# icewerx_Carrier.net
KiCad netlist of a schematic drawn in EAGLE
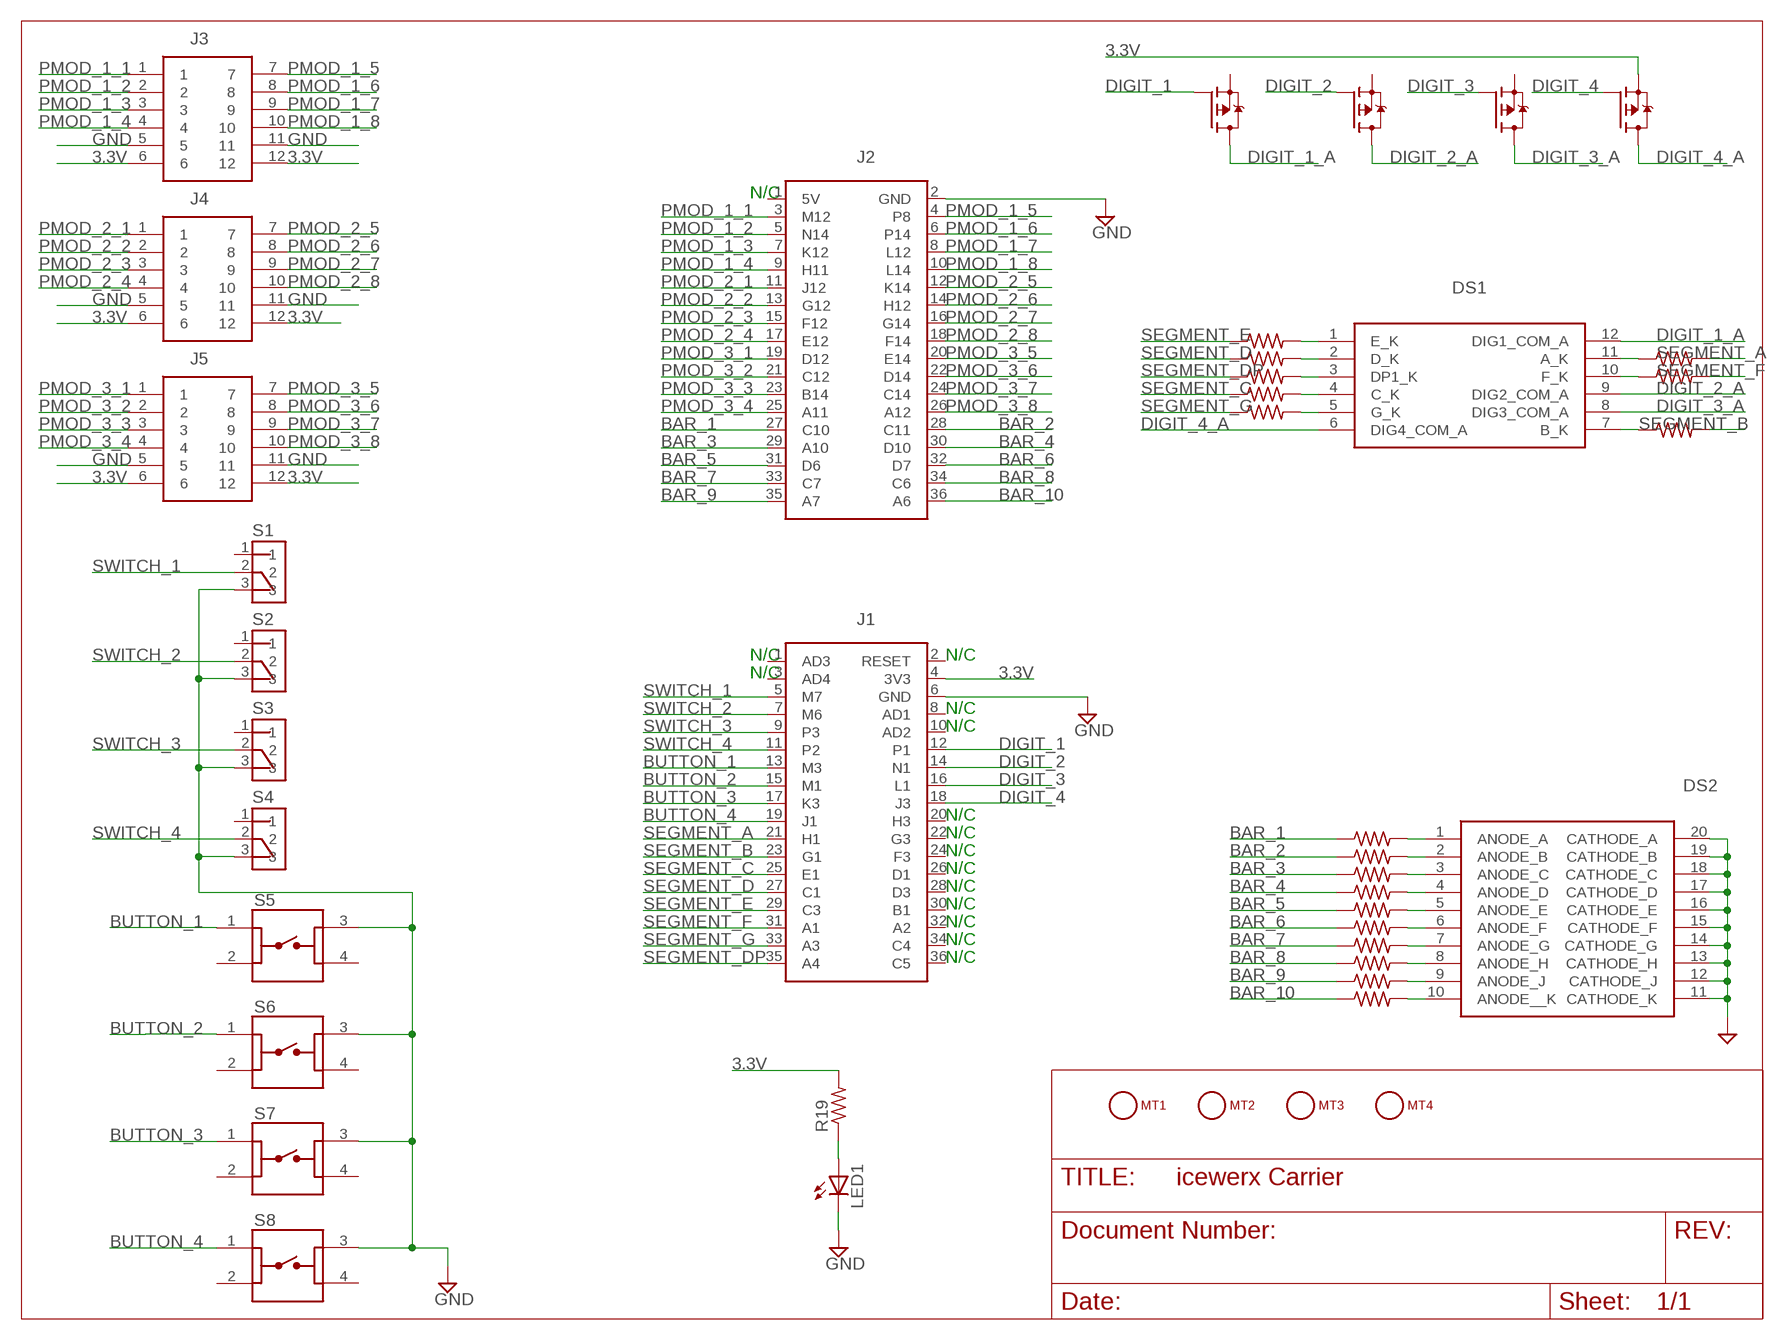
[diagram p0: schematic, sheet 1]

(export (version "E")
  (design (tool "Eeschema 10.0.6"))
  (components
    (comp (ref "DS1")
      (value "LDQ-M282RI")
      (footprint "eagle-import:LDQM282RI")
      (fields (field (name "MOUSER_PART_NUMBER") "696-LDQ-M282RI"))
      (libsource (lib "eagle-import") (part "LDQ-M282RI"))
    )
    (comp (ref "DS2")
      (value "LTA-1000G")
      (footprint "eagle-import:DIPS762W50P254L2527H825Q20N")
      (fields (field (name "MOUSER_PART_NUMBER") "859-LTA-1000G"))
      (libsource (lib "eagle-import") (part "LTA-1000G"))
    )
    (comp (ref "J1")
      (value "ICEWERX-PL2")
      (footprint "eagle-import:TE_4-1734506-1")
      (libsource (lib "eagle-import") (part "ICEWERX-PL2"))
    )
    (comp (ref "J2")
      (value "ICEWERX-PL3")
      (footprint "eagle-import:TE_4-1734506-1")
      (libsource (lib "eagle-import") (part "ICEWERX-PL3"))
    )
    (comp (ref "J3")
      (value "PMOD-SOCKET-FOR-HOST-BOARD")
      (footprint "eagle-import:PMOD-SOCKET-FOR-HOST-BOARD")
      (libsource (lib "eagle-import") (part "PMOD-SOCKET-FOR-HOST-BOARD"))
    )
    (comp (ref "J4")
      (value "PMOD-SOCKET-FOR-HOST-BOARD")
      (footprint "eagle-import:PMOD-SOCKET-FOR-HOST-BOARD")
      (libsource (lib "eagle-import") (part "PMOD-SOCKET-FOR-HOST-BOARD"))
    )
    (comp (ref "J5")
      (value "PMOD-SOCKET-FOR-HOST-BOARD")
      (footprint "eagle-import:PMOD-SOCKET-FOR-HOST-BOARD")
      (libsource (lib "eagle-import") (part "PMOD-SOCKET-FOR-HOST-BOARD"))
    )
    (comp (ref "LED1")
      (value "LED5MM")
      (footprint "eagle-import:LED5MM")
      (libsource (lib "eagle-import") (part "LED5MM"))
    )
    (comp (ref "MT1")
      (value "MOUNTING_HOLE-125_250_ROUND")
      (footprint "eagle-import:MT_125_250")
      (libsource (lib "eagle-import") (part "MOUNTING_HOLE-125_250_ROUND"))
    )
    (comp (ref "MT2")
      (value "MOUNTING_HOLE-125_250_ROUND")
      (footprint "eagle-import:MT_125_250")
      (libsource (lib "eagle-import") (part "MOUNTING_HOLE-125_250_ROUND"))
    )
    (comp (ref "MT3")
      (value "MOUNTING_HOLE-125_250_ROUND")
      (footprint "eagle-import:MT_125_250")
      (libsource (lib "eagle-import") (part "MOUNTING_HOLE-125_250_ROUND"))
    )
    (comp (ref "MT4")
      (value "MOUNTING_HOLE-125_250_ROUND")
      (footprint "eagle-import:MT_125_250")
      (libsource (lib "eagle-import") (part "MOUNTING_HOLE-125_250_ROUND"))
    )
    (comp (ref "Q1")
      (value "NX2301P")
      (footprint "eagle-import:SOT95P230X110-3N")
      (fields (field (name "MANUFACTURER") "Nexperia"))
      (libsource (lib "eagle-import") (part "NX2301P"))
    )
    (comp (ref "Q2")
      (value "NX2301P")
      (footprint "eagle-import:SOT95P230X110-3N")
      (fields (field (name "MANUFACTURER") "Nexperia"))
      (libsource (lib "eagle-import") (part "NX2301P"))
    )
    (comp (ref "Q3")
      (value "NX2301P")
      (footprint "eagle-import:SOT95P230X110-3N")
      (fields (field (name "MANUFACTURER") "Nexperia"))
      (libsource (lib "eagle-import") (part "NX2301P"))
    )
    (comp (ref "Q4")
      (value "NX2301P")
      (footprint "eagle-import:SOT95P230X110-3N")
      (fields (field (name "MANUFACTURER") "Nexperia"))
      (libsource (lib "eagle-import") (part "NX2301P"))
    )
    (comp (ref "R1")
      (value "R-US_0204/5")
      (footprint "eagle-import:0204_5")
      (libsource (lib "eagle-import") (part "R-US_0204/5"))
    )
    (comp (ref "R2")
      (value "R-US_0204/5")
      (footprint "eagle-import:0204_5")
      (libsource (lib "eagle-import") (part "R-US_0204/5"))
    )
    (comp (ref "R3")
      (value "R-US_0204/5")
      (footprint "eagle-import:0204_5")
      (libsource (lib "eagle-import") (part "R-US_0204/5"))
    )
    (comp (ref "R4")
      (value "R-US_0204/5")
      (footprint "eagle-import:0204_5")
      (libsource (lib "eagle-import") (part "R-US_0204/5"))
    )
    (comp (ref "R5")
      (value "R-US_0204/5")
      (footprint "eagle-import:0204_5")
      (libsource (lib "eagle-import") (part "R-US_0204/5"))
    )
    (comp (ref "R6")
      (value "R-US_0204/5")
      (footprint "eagle-import:0204_5")
      (libsource (lib "eagle-import") (part "R-US_0204/5"))
    )
    (comp (ref "R7")
      (value "R-US_0204/5")
      (footprint "eagle-import:0204_5")
      (libsource (lib "eagle-import") (part "R-US_0204/5"))
    )
    (comp (ref "R8")
      (value "R-US_0204/5")
      (footprint "eagle-import:0204_5")
      (libsource (lib "eagle-import") (part "R-US_0204/5"))
    )
    (comp (ref "R9")
      (value "R-US_0204/5")
      (footprint "eagle-import:0204_5")
      (libsource (lib "eagle-import") (part "R-US_0204/5"))
    )
    (comp (ref "R10")
      (value "R-US_0204/5")
      (footprint "eagle-import:0204_5")
      (libsource (lib "eagle-import") (part "R-US_0204/5"))
    )
    (comp (ref "R11")
      (value "R-US_0204/5")
      (footprint "eagle-import:0204_5")
      (libsource (lib "eagle-import") (part "R-US_0204/5"))
    )
    (comp (ref "R12")
      (value "R-US_0204/5")
      (footprint "eagle-import:0204_5")
      (libsource (lib "eagle-import") (part "R-US_0204/5"))
    )
    (comp (ref "R13")
      (value "R-US_0204/5")
      (footprint "eagle-import:0204_5")
      (libsource (lib "eagle-import") (part "R-US_0204/5"))
    )
    (comp (ref "R14")
      (value "R-US_0204/5")
      (footprint "eagle-import:0204_5")
      (libsource (lib "eagle-import") (part "R-US_0204/5"))
    )
    (comp (ref "R15")
      (value "R-US_0204/5")
      (footprint "eagle-import:0204_5")
      (libsource (lib "eagle-import") (part "R-US_0204/5"))
    )
    (comp (ref "R16")
      (value "R-US_0204/5")
      (footprint "eagle-import:0204_5")
      (libsource (lib "eagle-import") (part "R-US_0204/5"))
    )
    (comp (ref "R17")
      (value "R-US_0204/5")
      (footprint "eagle-import:0204_5")
      (libsource (lib "eagle-import") (part "R-US_0204/5"))
    )
    (comp (ref "R18")
      (value "R-US_0204/5")
      (footprint "eagle-import:0204_5")
      (libsource (lib "eagle-import") (part "R-US_0204/5"))
    )
    (comp (ref "R19")
      (value "R-US_0204/5")
      (footprint "eagle-import:0204_5")
      (libsource (lib "eagle-import") (part "R-US_0204/5"))
    )
    (comp (ref "S1")
      (value "OS102011MS2QN1")
      (footprint "eagle-import:SW_OS102011MS2QN1")
      (fields (field (name "MANUFACTURER") "C&K"))
      (libsource (lib "eagle-import") (part "OS102011MS2QN1"))
    )
    (comp (ref "S2")
      (value "OS102011MS2QN1")
      (footprint "eagle-import:SW_OS102011MS2QN1")
      (fields (field (name "MANUFACTURER") "C&K"))
      (libsource (lib "eagle-import") (part "OS102011MS2QN1"))
    )
    (comp (ref "S3")
      (value "OS102011MS2QN1")
      (footprint "eagle-import:SW_OS102011MS2QN1")
      (fields (field (name "MANUFACTURER") "C&K"))
      (libsource (lib "eagle-import") (part "OS102011MS2QN1"))
    )
    (comp (ref "S4")
      (value "OS102011MS2QN1")
      (footprint "eagle-import:SW_OS102011MS2QN1")
      (fields (field (name "MANUFACTURER") "C&K"))
      (libsource (lib "eagle-import") (part "OS102011MS2QN1"))
    )
    (comp (ref "S5")
      (value "1825910-7")
      (footprint "eagle-import:SW_1825910-7")
      (fields (field (name "MANUFACTURER") "TE Connectivity"))
      (libsource (lib "eagle-import") (part "1825910-7"))
    )
    (comp (ref "S6")
      (value "1825910-7")
      (footprint "eagle-import:SW_1825910-7")
      (fields (field (name "MANUFACTURER") "TE Connectivity"))
      (libsource (lib "eagle-import") (part "1825910-7"))
    )
    (comp (ref "S7")
      (value "1825910-7")
      (footprint "eagle-import:SW_1825910-7")
      (fields (field (name "MANUFACTURER") "TE Connectivity"))
      (libsource (lib "eagle-import") (part "1825910-7"))
    )
    (comp (ref "S8")
      (value "1825910-7")
      (footprint "eagle-import:SW_1825910-7")
      (fields (field (name "MANUFACTURER") "TE Connectivity"))
      (libsource (lib "eagle-import") (part "1825910-7"))
    )
  )
  (nets
    (net (code "1") (name "/3.3V") (class "Default")
      (node (ref "J1") (pin "4") (pinfunction "3V3_4") (pintype "bidirectional"))
      (node (ref "J3") (pin "12") (pinfunction "12_12") (pintype "bidirectional"))
      (node (ref "J3") (pin "6") (pinfunction "6_6") (pintype "bidirectional"))
      (node (ref "J4") (pin "12") (pinfunction "12_12") (pintype "bidirectional"))
      (node (ref "J4") (pin "6") (pinfunction "6_6") (pintype "bidirectional"))
      (node (ref "J5") (pin "12") (pinfunction "12_12") (pintype "bidirectional"))
      (node (ref "J5") (pin "6") (pinfunction "6_6") (pintype "bidirectional"))
      (node (ref "Q4") (pin "2") (pinfunction "S_2") (pintype "passive"))
      (node (ref "R19") (pin "2") (pinfunction "2_2") (pintype "passive"))
    )
    (net (code "2") (name "/BAR_1") (class "Default")
      (node (ref "J2") (pin "27") (pinfunction "C10_27") (pintype "bidirectional"))
      (node (ref "R1") (pin "1") (pinfunction "1_1") (pintype "passive"))
    )
    (net (code "3") (name "/BAR_2") (class "Default")
      (node (ref "J2") (pin "28") (pinfunction "C11_28") (pintype "bidirectional"))
      (node (ref "R2") (pin "1") (pinfunction "1_1") (pintype "passive"))
    )
    (net (code "4") (name "/BAR_3") (class "Default")
      (node (ref "J2") (pin "29") (pinfunction "A10_29") (pintype "bidirectional"))
      (node (ref "R3") (pin "1") (pinfunction "1_1") (pintype "passive"))
    )
    (net (code "5") (name "/BAR_4") (class "Default")
      (node (ref "J2") (pin "30") (pinfunction "D10_30") (pintype "bidirectional"))
      (node (ref "R5") (pin "1") (pinfunction "1_1") (pintype "passive"))
    )
    (net (code "6") (name "/BAR_5") (class "Default")
      (node (ref "J2") (pin "31") (pinfunction "D6_31") (pintype "bidirectional"))
      (node (ref "R4") (pin "1") (pinfunction "1_1") (pintype "passive"))
    )
    (net (code "7") (name "/BAR_6") (class "Default")
      (node (ref "J2") (pin "32") (pinfunction "D7_32") (pintype "bidirectional"))
      (node (ref "R6") (pin "1") (pinfunction "1_1") (pintype "passive"))
    )
    (net (code "8") (name "/BAR_7") (class "Default")
      (node (ref "J2") (pin "33") (pinfunction "C7_33") (pintype "bidirectional"))
      (node (ref "R7") (pin "1") (pinfunction "1_1") (pintype "passive"))
    )
    (net (code "9") (name "/BAR_8") (class "Default")
      (node (ref "J2") (pin "34") (pinfunction "C6_34") (pintype "bidirectional"))
      (node (ref "R8") (pin "1") (pinfunction "1_1") (pintype "passive"))
    )
    (net (code "10") (name "/BAR_9") (class "Default")
      (node (ref "J2") (pin "35") (pinfunction "A7_35") (pintype "bidirectional"))
      (node (ref "R10") (pin "1") (pinfunction "1_1") (pintype "passive"))
    )
    (net (code "11") (name "/BAR_10") (class "Default")
      (node (ref "J2") (pin "36") (pinfunction "A6_36") (pintype "bidirectional"))
      (node (ref "R9") (pin "1") (pinfunction "1_1") (pintype "passive"))
    )
    (net (code "12") (name "/BUTTON_1") (class "Default")
      (node (ref "J1") (pin "13") (pinfunction "M3_13") (pintype "bidirectional"))
      (node (ref "S5") (pin "1") (pinfunction "1_1") (pintype "passive"))
    )
    (net (code "13") (name "/BUTTON_2") (class "Default")
      (node (ref "J1") (pin "15") (pinfunction "M1_15") (pintype "bidirectional"))
      (node (ref "S6") (pin "1") (pinfunction "1_1") (pintype "passive"))
    )
    (net (code "14") (name "/BUTTON_3") (class "Default")
      (node (ref "J1") (pin "17") (pinfunction "K3_17") (pintype "bidirectional"))
      (node (ref "S7") (pin "1") (pinfunction "1_1") (pintype "passive"))
    )
    (net (code "15") (name "/BUTTON_4") (class "Default")
      (node (ref "J1") (pin "19") (pinfunction "J1_19") (pintype "bidirectional"))
      (node (ref "S8") (pin "1") (pinfunction "1_1") (pintype "passive"))
    )
    (net (code "16") (name "/DIGIT_1") (class "Default")
      (node (ref "J1") (pin "12") (pinfunction "P1_12") (pintype "bidirectional"))
      (node (ref "Q1") (pin "1") (pinfunction "G_1") (pintype "passive"))
    )
    (net (code "17") (name "/DIGIT_1_A") (class "Default")
      (node (ref "DS1") (pin "12") (pinfunction "DIG1_COM_A_12") (pintype "bidirectional"))
      (node (ref "Q1") (pin "3") (pinfunction "D_3") (pintype "passive"))
    )
    (net (code "18") (name "/DIGIT_2") (class "Default")
      (node (ref "J1") (pin "14") (pinfunction "N1_14") (pintype "bidirectional"))
      (node (ref "Q2") (pin "1") (pinfunction "G_1") (pintype "passive"))
    )
    (net (code "19") (name "/DIGIT_2_A") (class "Default")
      (node (ref "DS1") (pin "9") (pinfunction "DIG2_COM_A_9") (pintype "bidirectional"))
      (node (ref "Q2") (pin "3") (pinfunction "D_3") (pintype "passive"))
    )
    (net (code "20") (name "/DIGIT_3") (class "Default")
      (node (ref "J1") (pin "16") (pinfunction "L1_16") (pintype "bidirectional"))
      (node (ref "Q3") (pin "1") (pinfunction "G_1") (pintype "passive"))
    )
    (net (code "21") (name "/DIGIT_3_A") (class "Default")
      (node (ref "DS1") (pin "8") (pinfunction "DIG3_COM_A_8") (pintype "bidirectional"))
      (node (ref "Q3") (pin "3") (pinfunction "D_3") (pintype "passive"))
    )
    (net (code "22") (name "/DIGIT_4") (class "Default")
      (node (ref "J1") (pin "18") (pinfunction "J3_18") (pintype "bidirectional"))
      (node (ref "Q4") (pin "1") (pinfunction "G_1") (pintype "passive"))
    )
    (net (code "23") (name "/DIGIT_4_A") (class "Default")
      (node (ref "DS1") (pin "6") (pinfunction "DIG4_COM_A_6") (pintype "bidirectional"))
      (node (ref "Q4") (pin "3") (pinfunction "D_3") (pintype "passive"))
    )
    (net (code "24") (name "/PMOD_1_1") (class "Default")
      (node (ref "J2") (pin "3") (pinfunction "M12_3") (pintype "bidirectional"))
      (node (ref "J3") (pin "1") (pinfunction "1_1") (pintype "bidirectional"))
    )
    (net (code "25") (name "/PMOD_1_2") (class "Default")
      (node (ref "J2") (pin "5") (pinfunction "N14_5") (pintype "bidirectional"))
      (node (ref "J3") (pin "2") (pinfunction "2_2") (pintype "bidirectional"))
    )
    (net (code "26") (name "/PMOD_1_3") (class "Default")
      (node (ref "J2") (pin "7") (pinfunction "K12_7") (pintype "bidirectional"))
      (node (ref "J3") (pin "3") (pinfunction "3_3") (pintype "bidirectional"))
    )
    (net (code "27") (name "/PMOD_1_4") (class "Default")
      (node (ref "J2") (pin "9") (pinfunction "H11_9") (pintype "bidirectional"))
      (node (ref "J3") (pin "4") (pinfunction "4_4") (pintype "bidirectional"))
    )
    (net (code "28") (name "/PMOD_1_5") (class "Default")
      (node (ref "J2") (pin "4") (pinfunction "P8_4") (pintype "bidirectional"))
      (node (ref "J3") (pin "7") (pinfunction "7_7") (pintype "bidirectional"))
    )
    (net (code "29") (name "/PMOD_1_6") (class "Default")
      (node (ref "J2") (pin "6") (pinfunction "P14_6") (pintype "bidirectional"))
      (node (ref "J3") (pin "8") (pinfunction "8_8") (pintype "bidirectional"))
    )
    (net (code "30") (name "/PMOD_1_7") (class "Default")
      (node (ref "J2") (pin "8") (pinfunction "L12_8") (pintype "bidirectional"))
      (node (ref "J3") (pin "9") (pinfunction "9_9") (pintype "bidirectional"))
    )
    (net (code "31") (name "/PMOD_1_8") (class "Default")
      (node (ref "J2") (pin "10") (pinfunction "L14_10") (pintype "bidirectional"))
      (node (ref "J3") (pin "10") (pinfunction "10_10") (pintype "bidirectional"))
    )
    (net (code "32") (name "/PMOD_2_1") (class "Default")
      (node (ref "J2") (pin "11") (pinfunction "J12_11") (pintype "bidirectional"))
      (node (ref "J4") (pin "1") (pinfunction "1_1") (pintype "bidirectional"))
    )
    (net (code "33") (name "/PMOD_2_2") (class "Default")
      (node (ref "J2") (pin "13") (pinfunction "G12_13") (pintype "bidirectional"))
      (node (ref "J4") (pin "2") (pinfunction "2_2") (pintype "bidirectional"))
    )
    (net (code "34") (name "/PMOD_2_3") (class "Default")
      (node (ref "J2") (pin "15") (pinfunction "F12_15") (pintype "bidirectional"))
      (node (ref "J4") (pin "3") (pinfunction "3_3") (pintype "bidirectional"))
    )
    (net (code "35") (name "/PMOD_2_4") (class "Default")
      (node (ref "J2") (pin "17") (pinfunction "E12_17") (pintype "bidirectional"))
      (node (ref "J4") (pin "4") (pinfunction "4_4") (pintype "bidirectional"))
    )
    (net (code "36") (name "/PMOD_2_5") (class "Default")
      (node (ref "J2") (pin "12") (pinfunction "K14_12") (pintype "bidirectional"))
      (node (ref "J4") (pin "7") (pinfunction "7_7") (pintype "bidirectional"))
    )
    (net (code "37") (name "/PMOD_2_6") (class "Default")
      (node (ref "J2") (pin "14") (pinfunction "H12_14") (pintype "bidirectional"))
      (node (ref "J4") (pin "8") (pinfunction "8_8") (pintype "bidirectional"))
    )
    (net (code "38") (name "/PMOD_2_7") (class "Default")
      (node (ref "J2") (pin "16") (pinfunction "G14_16") (pintype "bidirectional"))
      (node (ref "J4") (pin "9") (pinfunction "9_9") (pintype "bidirectional"))
    )
    (net (code "39") (name "/PMOD_2_8") (class "Default")
      (node (ref "J2") (pin "18") (pinfunction "F14_18") (pintype "bidirectional"))
      (node (ref "J4") (pin "10") (pinfunction "10_10") (pintype "bidirectional"))
    )
    (net (code "40") (name "/PMOD_3_1") (class "Default")
      (node (ref "J2") (pin "19") (pinfunction "D12_19") (pintype "bidirectional"))
      (node (ref "J5") (pin "1") (pinfunction "1_1") (pintype "bidirectional"))
    )
    (net (code "41") (name "/PMOD_3_2") (class "Default")
      (node (ref "J2") (pin "21") (pinfunction "C12_21") (pintype "bidirectional"))
      (node (ref "J5") (pin "2") (pinfunction "2_2") (pintype "bidirectional"))
    )
    (net (code "42") (name "/PMOD_3_3") (class "Default")
      (node (ref "J2") (pin "23") (pinfunction "B14_23") (pintype "bidirectional"))
      (node (ref "J5") (pin "3") (pinfunction "3_3") (pintype "bidirectional"))
    )
    (net (code "43") (name "/PMOD_3_4") (class "Default")
      (node (ref "J2") (pin "25") (pinfunction "A11_25") (pintype "bidirectional"))
      (node (ref "J5") (pin "4") (pinfunction "4_4") (pintype "bidirectional"))
    )
    (net (code "44") (name "/PMOD_3_5") (class "Default")
      (node (ref "J2") (pin "20") (pinfunction "E14_20") (pintype "bidirectional"))
      (node (ref "J5") (pin "7") (pinfunction "7_7") (pintype "bidirectional"))
    )
    (net (code "45") (name "/PMOD_3_6") (class "Default")
      (node (ref "J2") (pin "22") (pinfunction "D14_22") (pintype "bidirectional"))
      (node (ref "J5") (pin "8") (pinfunction "8_8") (pintype "bidirectional"))
    )
    (net (code "46") (name "/PMOD_3_7") (class "Default")
      (node (ref "J2") (pin "24") (pinfunction "C14_24") (pintype "bidirectional"))
      (node (ref "J5") (pin "9") (pinfunction "9_9") (pintype "bidirectional"))
    )
    (net (code "47") (name "/PMOD_3_8") (class "Default")
      (node (ref "J2") (pin "26") (pinfunction "A12_26") (pintype "bidirectional"))
      (node (ref "J5") (pin "10") (pinfunction "10_10") (pintype "bidirectional"))
    )
    (net (code "48") (name "/SEGMENT_A") (class "Default")
      (node (ref "J1") (pin "21") (pinfunction "H1_21") (pintype "bidirectional"))
      (node (ref "R16") (pin "2") (pinfunction "2_2") (pintype "passive"))
    )
    (net (code "49") (name "/SEGMENT_B") (class "Default")
      (node (ref "J1") (pin "23") (pinfunction "G1_23") (pintype "bidirectional"))
      (node (ref "R18") (pin "2") (pinfunction "2_2") (pintype "passive"))
    )
    (net (code "50") (name "/SEGMENT_C") (class "Default")
      (node (ref "J1") (pin "25") (pinfunction "E1_25") (pintype "bidirectional"))
      (node (ref "R14") (pin "1") (pinfunction "1_1") (pintype "passive"))
    )
    (net (code "51") (name "/SEGMENT_D") (class "Default")
      (node (ref "J1") (pin "27") (pinfunction "C1_27") (pintype "bidirectional"))
      (node (ref "R12") (pin "1") (pinfunction "1_1") (pintype "passive"))
    )
    (net (code "52") (name "/SEGMENT_DP") (class "Default")
      (node (ref "J1") (pin "35") (pinfunction "A4_35") (pintype "bidirectional"))
      (node (ref "R13") (pin "1") (pinfunction "1_1") (pintype "passive"))
    )
    (net (code "53") (name "/SEGMENT_E") (class "Default")
      (node (ref "J1") (pin "29") (pinfunction "C3_29") (pintype "bidirectional"))
      (node (ref "R11") (pin "1") (pinfunction "1_1") (pintype "passive"))
    )
    (net (code "54") (name "/SEGMENT_F") (class "Default")
      (node (ref "J1") (pin "31") (pinfunction "A1_31") (pintype "bidirectional"))
      (node (ref "R17") (pin "2") (pinfunction "2_2") (pintype "passive"))
    )
    (net (code "55") (name "/SEGMENT_G") (class "Default")
      (node (ref "J1") (pin "33") (pinfunction "A3_33") (pintype "bidirectional"))
      (node (ref "R15") (pin "1") (pinfunction "1_1") (pintype "passive"))
    )
    (net (code "56") (name "/SWITCH_1") (class "Default")
      (node (ref "J1") (pin "5") (pinfunction "M7_5") (pintype "bidirectional"))
      (node (ref "S1") (pin "2") (pinfunction "2_2") (pintype "passive"))
    )
    (net (code "57") (name "/SWITCH_2") (class "Default")
      (node (ref "J1") (pin "7") (pinfunction "M6_7") (pintype "bidirectional"))
      (node (ref "S2") (pin "2") (pinfunction "2_2") (pintype "passive"))
    )
    (net (code "58") (name "/SWITCH_3") (class "Default")
      (node (ref "J1") (pin "9") (pinfunction "P3_9") (pintype "bidirectional"))
      (node (ref "S3") (pin "2") (pinfunction "2_2") (pintype "passive"))
    )
    (net (code "59") (name "/SWITCH_4") (class "Default")
      (node (ref "J1") (pin "11") (pinfunction "P2_11") (pintype "bidirectional"))
      (node (ref "S4") (pin "2") (pinfunction "2_2") (pintype "passive"))
    )
    (net (code "60") (name "GND") (class "Default")
      (node (ref "DS2") (pin "11") (pinfunction "CATHODE_K_11") (pintype "bidirectional"))
      (node (ref "DS2") (pin "12") (pinfunction "CATHODE_J_12") (pintype "bidirectional"))
      (node (ref "DS2") (pin "13") (pinfunction "CATHODE_H_13") (pintype "bidirectional"))
      (node (ref "DS2") (pin "14") (pinfunction "CATHODE_G_14") (pintype "bidirectional"))
      (node (ref "DS2") (pin "15") (pinfunction "CATHODE_F_15") (pintype "bidirectional"))
      (node (ref "DS2") (pin "16") (pinfunction "CATHODE_E_16") (pintype "bidirectional"))
      (node (ref "DS2") (pin "17") (pinfunction "CATHODE_D_17") (pintype "bidirectional"))
      (node (ref "DS2") (pin "18") (pinfunction "CATHODE_C_18") (pintype "bidirectional"))
      (node (ref "DS2") (pin "19") (pinfunction "CATHODE_B_19") (pintype "bidirectional"))
      (node (ref "DS2") (pin "20") (pinfunction "CATHODE_A_20") (pintype "bidirectional"))
      (node (ref "J1") (pin "6") (pinfunction "GND_6") (pintype "bidirectional"))
      (node (ref "J2") (pin "2") (pinfunction "GND_2") (pintype "bidirectional"))
      (node (ref "J3") (pin "11") (pinfunction "11_11") (pintype "bidirectional"))
      (node (ref "J3") (pin "5") (pinfunction "5_5") (pintype "bidirectional"))
      (node (ref "J4") (pin "11") (pinfunction "11_11") (pintype "bidirectional"))
      (node (ref "J4") (pin "5") (pinfunction "5_5") (pintype "bidirectional"))
      (node (ref "J5") (pin "11") (pinfunction "11_11") (pintype "bidirectional"))
      (node (ref "J5") (pin "5") (pinfunction "5_5") (pintype "bidirectional"))
      (node (ref "LED1") (pin "K") (pinfunction "C_K") (pintype "passive"))
      (node (ref "S1") (pin "3") (pinfunction "3_3") (pintype "passive"))
      (node (ref "S2") (pin "3") (pinfunction "3_3") (pintype "passive"))
      (node (ref "S3") (pin "3") (pinfunction "3_3") (pintype "passive"))
      (node (ref "S4") (pin "3") (pinfunction "3_3") (pintype "passive"))
      (node (ref "S5") (pin "3") (pinfunction "3_3") (pintype "passive"))
      (node (ref "S6") (pin "3") (pinfunction "3_3") (pintype "passive"))
      (node (ref "S7") (pin "3") (pinfunction "3_3") (pintype "passive"))
      (node (ref "S8") (pin "3") (pinfunction "3_3") (pintype "passive"))
    )
    (net (code "61") (name "Net-(DS1-A_K)") (class "Default")
      (node (ref "DS1") (pin "11") (pinfunction "A_K_11") (pintype "bidirectional"))
      (node (ref "R16") (pin "1") (pinfunction "1_1") (pintype "passive"))
    )
    (net (code "62") (name "Net-(DS1-B_K)") (class "Default")
      (node (ref "DS1") (pin "7") (pinfunction "B_K_7") (pintype "bidirectional"))
      (node (ref "R18") (pin "1") (pinfunction "1_1") (pintype "passive"))
    )
    (net (code "63") (name "Net-(DS1-C_K)") (class "Default")
      (node (ref "DS1") (pin "4") (pinfunction "C_K_4") (pintype "bidirectional"))
      (node (ref "R14") (pin "2") (pinfunction "2_2") (pintype "passive"))
    )
    (net (code "64") (name "Net-(DS1-DP1_K)") (class "Default")
      (node (ref "DS1") (pin "3") (pinfunction "DP1_K_3") (pintype "bidirectional"))
      (node (ref "R13") (pin "2") (pinfunction "2_2") (pintype "passive"))
    )
    (net (code "65") (name "Net-(DS1-D_K)") (class "Default")
      (node (ref "DS1") (pin "2") (pinfunction "D_K_2") (pintype "bidirectional"))
      (node (ref "R12") (pin "2") (pinfunction "2_2") (pintype "passive"))
    )
    (net (code "66") (name "Net-(DS1-E_K)") (class "Default")
      (node (ref "DS1") (pin "1") (pinfunction "E_K_1") (pintype "bidirectional"))
      (node (ref "R11") (pin "2") (pinfunction "2_2") (pintype "passive"))
    )
    (net (code "67") (name "Net-(DS1-F_K)") (class "Default")
      (node (ref "DS1") (pin "10") (pinfunction "F_K_10") (pintype "bidirectional"))
      (node (ref "R17") (pin "1") (pinfunction "1_1") (pintype "passive"))
    )
    (net (code "68") (name "Net-(DS1-G_K)") (class "Default")
      (node (ref "DS1") (pin "5") (pinfunction "G_K_5") (pintype "bidirectional"))
      (node (ref "R15") (pin "2") (pinfunction "2_2") (pintype "passive"))
    )
    (net (code "69") (name "Net-(DS2-ANODE_A)") (class "Default")
      (node (ref "DS2") (pin "1") (pinfunction "ANODE_A_1") (pintype "bidirectional"))
      (node (ref "R1") (pin "2") (pinfunction "2_2") (pintype "passive"))
    )
    (net (code "70") (name "Net-(DS2-ANODE_B)") (class "Default")
      (node (ref "DS2") (pin "2") (pinfunction "ANODE_B_2") (pintype "bidirectional"))
      (node (ref "R2") (pin "2") (pinfunction "2_2") (pintype "passive"))
    )
    (net (code "71") (name "Net-(DS2-ANODE_C)") (class "Default")
      (node (ref "DS2") (pin "3") (pinfunction "ANODE_C_3") (pintype "bidirectional"))
      (node (ref "R3") (pin "2") (pinfunction "2_2") (pintype "passive"))
    )
    (net (code "72") (name "Net-(DS2-ANODE_D)") (class "Default")
      (node (ref "DS2") (pin "4") (pinfunction "ANODE_D_4") (pintype "bidirectional"))
      (node (ref "R5") (pin "2") (pinfunction "2_2") (pintype "passive"))
    )
    (net (code "73") (name "Net-(DS2-ANODE_E)") (class "Default")
      (node (ref "DS2") (pin "5") (pinfunction "ANODE_E_5") (pintype "bidirectional"))
      (node (ref "R4") (pin "2") (pinfunction "2_2") (pintype "passive"))
    )
    (net (code "74") (name "Net-(DS2-ANODE_F)") (class "Default")
      (node (ref "DS2") (pin "6") (pinfunction "ANODE_F_6") (pintype "bidirectional"))
      (node (ref "R6") (pin "2") (pinfunction "2_2") (pintype "passive"))
    )
    (net (code "75") (name "Net-(DS2-ANODE_G)") (class "Default")
      (node (ref "DS2") (pin "7") (pinfunction "ANODE_G_7") (pintype "bidirectional"))
      (node (ref "R7") (pin "2") (pinfunction "2_2") (pintype "passive"))
    )
    (net (code "76") (name "Net-(DS2-ANODE_H)") (class "Default")
      (node (ref "DS2") (pin "8") (pinfunction "ANODE_H_8") (pintype "bidirectional"))
      (node (ref "R8") (pin "2") (pinfunction "2_2") (pintype "passive"))
    )
    (net (code "77") (name "Net-(DS2-ANODE_J)") (class "Default")
      (node (ref "DS2") (pin "9") (pinfunction "ANODE_J_9") (pintype "bidirectional"))
      (node (ref "R10") (pin "2") (pinfunction "2_2") (pintype "passive"))
    )
    (net (code "78") (name "Net-(DS2-ANODE__K)") (class "Default")
      (node (ref "DS2") (pin "10") (pinfunction "ANODE__K_10") (pintype "bidirectional"))
      (node (ref "R9") (pin "2") (pinfunction "2_2") (pintype "passive"))
    )
    (net (code "79") (name "Net-(LED1-PadA)") (class "Default")
      (node (ref "LED1") (pin "A") (pinfunction "A_A") (pintype "passive"))
      (node (ref "R19") (pin "1") (pinfunction "1_1") (pintype "passive"))
    )
    (net (code "80") (name "unconnected-(J1-A2-Pad32)") (class "Default")
      (node (ref "J1") (pin "32") (pinfunction "A2_32") (pintype "bidirectional"))
    )
    (net (code "81") (name "unconnected-(J1-AD1-Pad8)") (class "Default")
      (node (ref "J1") (pin "8") (pinfunction "AD1_8") (pintype "bidirectional"))
    )
    (net (code "82") (name "unconnected-(J1-AD2-Pad10)") (class "Default")
      (node (ref "J1") (pin "10") (pinfunction "AD2_10") (pintype "bidirectional"))
    )
    (net (code "83") (name "unconnected-(J1-AD3-Pad1)") (class "Default")
      (node (ref "J1") (pin "1") (pinfunction "AD3_1") (pintype "bidirectional"))
    )
    (net (code "84") (name "unconnected-(J1-AD4-Pad3)") (class "Default")
      (node (ref "J1") (pin "3") (pinfunction "AD4_3") (pintype "bidirectional"))
    )
    (net (code "85") (name "unconnected-(J1-B1-Pad30)") (class "Default")
      (node (ref "J1") (pin "30") (pinfunction "B1_30") (pintype "bidirectional"))
    )
    (net (code "86") (name "unconnected-(J1-C4-Pad34)") (class "Default")
      (node (ref "J1") (pin "34") (pinfunction "C4_34") (pintype "bidirectional"))
    )
    (net (code "87") (name "unconnected-(J1-C5-Pad36)") (class "Default")
      (node (ref "J1") (pin "36") (pinfunction "C5_36") (pintype "bidirectional"))
    )
    (net (code "88") (name "unconnected-(J1-D1-Pad26)") (class "Default")
      (node (ref "J1") (pin "26") (pinfunction "D1_26") (pintype "bidirectional"))
    )
    (net (code "89") (name "unconnected-(J1-D3-Pad28)") (class "Default")
      (node (ref "J1") (pin "28") (pinfunction "D3_28") (pintype "bidirectional"))
    )
    (net (code "90") (name "unconnected-(J1-F3-Pad24)") (class "Default")
      (node (ref "J1") (pin "24") (pinfunction "F3_24") (pintype "bidirectional"))
    )
    (net (code "91") (name "unconnected-(J1-G3-Pad22)") (class "Default")
      (node (ref "J1") (pin "22") (pinfunction "G3_22") (pintype "bidirectional"))
    )
    (net (code "92") (name "unconnected-(J1-H3-Pad20)") (class "Default")
      (node (ref "J1") (pin "20") (pinfunction "H3_20") (pintype "bidirectional"))
    )
    (net (code "93") (name "unconnected-(J1-RESET-Pad2)") (class "Default")
      (node (ref "J1") (pin "2") (pinfunction "RESET_2") (pintype "bidirectional"))
    )
    (net (code "94") (name "unconnected-(J2-5V-Pad1)") (class "Default")
      (node (ref "J2") (pin "1") (pinfunction "5V_1") (pintype "bidirectional"))
    )
    (net (code "95") (name "unconnected-(MT1-P$1-Pad1)") (class "Default")
      (node (ref "MT1") (pin "1") (pinfunction "P$1_1") (pintype "bidirectional"))
    )
    (net (code "96") (name "unconnected-(MT2-P$1-Pad1)") (class "Default")
      (node (ref "MT2") (pin "1") (pinfunction "P$1_1") (pintype "bidirectional"))
    )
    (net (code "97") (name "unconnected-(MT3-P$1-Pad1)") (class "Default")
      (node (ref "MT3") (pin "1") (pinfunction "P$1_1") (pintype "bidirectional"))
    )
    (net (code "98") (name "unconnected-(MT4-P$1-Pad1)") (class "Default")
      (node (ref "MT4") (pin "1") (pinfunction "P$1_1") (pintype "bidirectional"))
    )
    (net (code "99") (name "unconnected-(Q1-S-Pad2)") (class "Default")
      (node (ref "Q1") (pin "2") (pinfunction "S_2") (pintype "passive"))
    )
    (net (code "100") (name "unconnected-(Q2-S-Pad2)") (class "Default")
      (node (ref "Q2") (pin "2") (pinfunction "S_2") (pintype "passive"))
    )
    (net (code "101") (name "unconnected-(Q3-S-Pad2)") (class "Default")
      (node (ref "Q3") (pin "2") (pinfunction "S_2") (pintype "passive"))
    )
    (net (code "102") (name "unconnected-(S1-Pad1)") (class "Default")
      (node (ref "S1") (pin "1") (pinfunction "1_1") (pintype "passive"))
    )
    (net (code "103") (name "unconnected-(S2-Pad1)") (class "Default")
      (node (ref "S2") (pin "1") (pinfunction "1_1") (pintype "passive"))
    )
    (net (code "104") (name "unconnected-(S3-Pad1)") (class "Default")
      (node (ref "S3") (pin "1") (pinfunction "1_1") (pintype "passive"))
    )
    (net (code "105") (name "unconnected-(S4-Pad1)") (class "Default")
      (node (ref "S4") (pin "1") (pinfunction "1_1") (pintype "passive"))
    )
    (net (code "106") (name "unconnected-(S5-Pad2)") (class "Default")
      (node (ref "S5") (pin "2") (pinfunction "2_2") (pintype "passive"))
    )
    (net (code "107") (name "unconnected-(S5-Pad4)") (class "Default")
      (node (ref "S5") (pin "4") (pinfunction "4_4") (pintype "passive"))
    )
    (net (code "108") (name "unconnected-(S6-Pad2)") (class "Default")
      (node (ref "S6") (pin "2") (pinfunction "2_2") (pintype "passive"))
    )
    (net (code "109") (name "unconnected-(S6-Pad4)") (class "Default")
      (node (ref "S6") (pin "4") (pinfunction "4_4") (pintype "passive"))
    )
    (net (code "110") (name "unconnected-(S7-Pad2)") (class "Default")
      (node (ref "S7") (pin "2") (pinfunction "2_2") (pintype "passive"))
    )
    (net (code "111") (name "unconnected-(S7-Pad4)") (class "Default")
      (node (ref "S7") (pin "4") (pinfunction "4_4") (pintype "passive"))
    )
    (net (code "112") (name "unconnected-(S8-Pad2)") (class "Default")
      (node (ref "S8") (pin "2") (pinfunction "2_2") (pintype "passive"))
    )
    (net (code "113") (name "unconnected-(S8-Pad4)") (class "Default")
      (node (ref "S8") (pin "4") (pinfunction "4_4") (pintype "passive"))
    )
  )
)
